# wahmodgnd.net
KiCad netlist of a schematic drawn in EAGLE
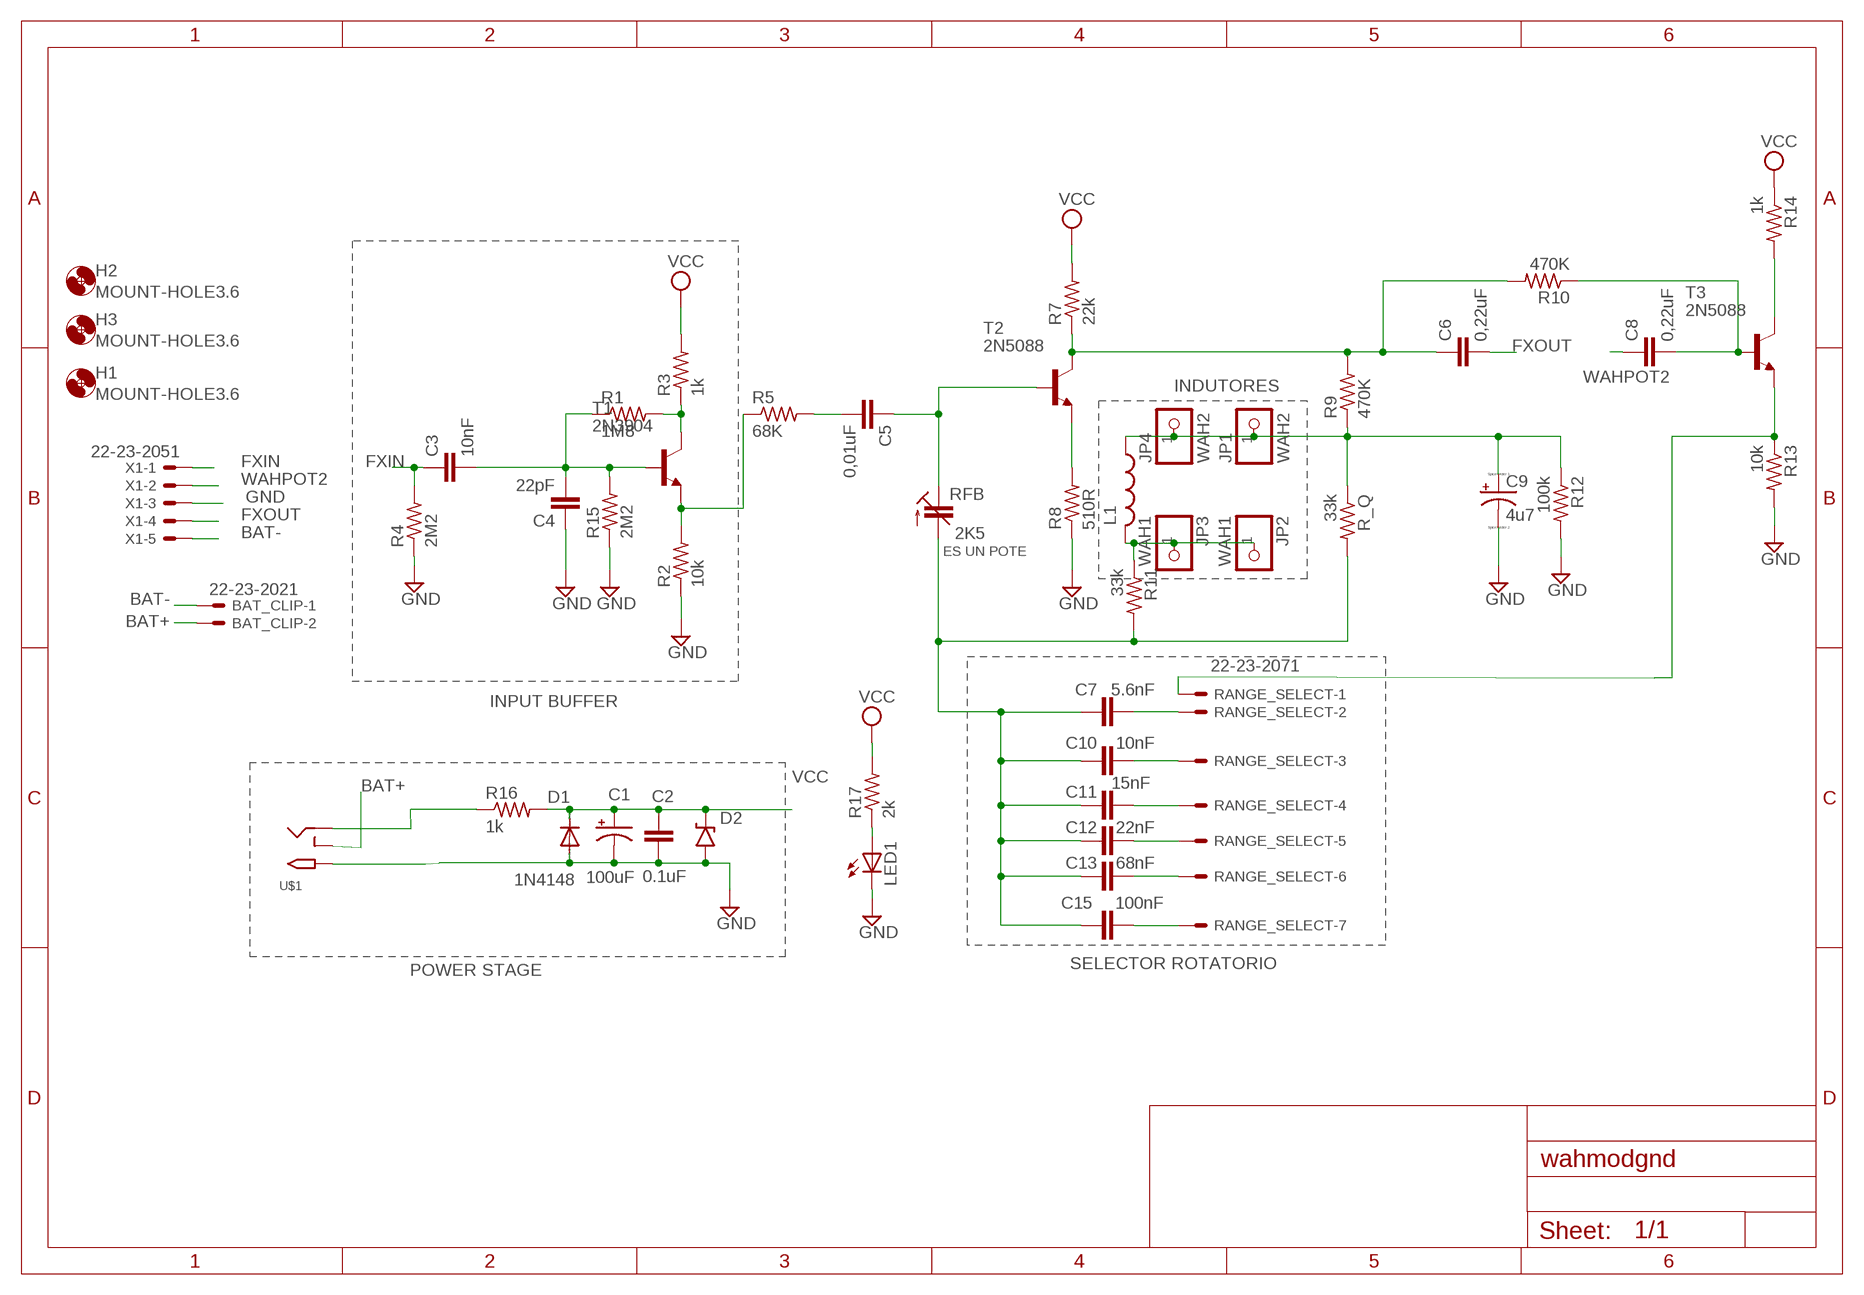
[diagram p0: schematic, sheet 1]

(export (version "E")
  (design (tool "Eeschema 10.0.6"))
  (components
    (comp (ref "BAT_CLIP")
      (value "22-23-2021")
      (footprint "eagle-import:22-23-2021")
      (fields (field (name "MF") "MOLEX"))
      (libsource (lib "eagle-import") (part "22-23-2021"))
    )
    (comp (ref "C1")
      (value "100uF")
      (footprint "eagle-import:E2,5-5")
      (libsource (lib "eagle-import") (part "CPOL-USE2.5-5"))
    )
    (comp (ref "C2")
      (value "0.1uF")
      (footprint "eagle-import:C025-025X050")
      (libsource (lib "eagle-import") (part "C-EU025-025X050"))
    )
    (comp (ref "C3")
      (value "10nF")
      (footprint "eagle-import:C050-025X075")
      (libsource (lib "eagle-import") (part "resistor_C-EU050-025X075"))
    )
    (comp (ref "C4")
      (value "22pF")
      (footprint "eagle-import:C050-025X075")
      (libsource (lib "eagle-import") (part "resistor_C-EU050-025X075"))
    )
    (comp (ref "C5")
      (value "0,01uF")
      (footprint "eagle-import:C050-035X075")
      (libsource (lib "eagle-import") (part "resistor_C-EU050-035X075"))
    )
    (comp (ref "C6")
      (value "0,22uF")
      (footprint "eagle-import:C050-035X075")
      (libsource (lib "eagle-import") (part "resistor_C-EU050-035X075"))
    )
    (comp (ref "C7")
      (value "5.6nF")
      (footprint "eagle-import:C050-030X075")
      (libsource (lib "eagle-import") (part "resistor_C-EU050-030X075"))
    )
    (comp (ref "C8")
      (value "0,22uF")
      (footprint "eagle-import:C050-035X075")
      (libsource (lib "eagle-import") (part "resistor_C-EU050-035X075"))
    )
    (comp (ref "C9")
      (value "4u7")
      (footprint "eagle-import:E2,5-6")
      (libsource (lib "eagle-import") (part "resistor_CPOL-USE2.5-6"))
    )
    (comp (ref "C10")
      (value "10nF")
      (footprint "eagle-import:C050-030X075")
      (libsource (lib "eagle-import") (part "resistor_C-EU050-030X075"))
    )
    (comp (ref "C11")
      (value "15nF")
      (footprint "eagle-import:C050-030X075")
      (libsource (lib "eagle-import") (part "resistor_C-EU050-030X075"))
    )
    (comp (ref "C12")
      (value "22nF")
      (footprint "eagle-import:C050-030X075")
      (libsource (lib "eagle-import") (part "resistor_C-EU050-030X075"))
    )
    (comp (ref "C13")
      (value "68nF")
      (footprint "eagle-import:C050-030X075")
      (libsource (lib "eagle-import") (part "resistor_C-EU050-030X075"))
    )
    (comp (ref "C15")
      (value "100nF")
      (footprint "eagle-import:C050-030X075")
      (libsource (lib "eagle-import") (part "resistor_C-EU050-030X075"))
    )
    (comp (ref "D1")
      (value "1N4148")
      (footprint "eagle-import:DO35-7")
      (libsource (lib "eagle-import") (part "1N4148DO35-7"))
    )
    (comp (ref "D2")
      (value "1N9ZENER")
      (footprint "eagle-import:DO35-3")
      (libsource (lib "eagle-import") (part "1N9ZENER"))
    )
    (comp (ref "H1")
      (value "MOUNT-HOLE3.6")
      (footprint "eagle-import:3,6")
      (libsource (lib "eagle-import") (part "MOUNT-HOLE3.6"))
    )
    (comp (ref "H2")
      (value "MOUNT-HOLE3.6")
      (footprint "eagle-import:3,6")
      (libsource (lib "eagle-import") (part "MOUNT-HOLE3.6"))
    )
    (comp (ref "H3")
      (value "MOUNT-HOLE3.6")
      (footprint "eagle-import:3,6")
      (libsource (lib "eagle-import") (part "MOUNT-HOLE3.6"))
    )
    (comp (ref "JP1")
      (value "WAH2")
      (footprint "eagle-import:1X01")
      (libsource (lib "eagle-import") (part "PINHD-1X1"))
    )
    (comp (ref "JP2")
      (value "WAH1")
      (footprint "eagle-import:1X01")
      (libsource (lib "eagle-import") (part "PINHD-1X1"))
    )
    (comp (ref "JP3")
      (value "WAH1")
      (footprint "eagle-import:1X01")
      (libsource (lib "eagle-import") (part "PINHD-1X1"))
    )
    (comp (ref "JP4")
      (value "WAH2")
      (footprint "eagle-import:1X01")
      (libsource (lib "eagle-import") (part "PINHD-1X1"))
    )
    (comp (ref "L1")
      (value "WAH")
      (footprint "eagle-import:WAH")
      (libsource (lib "eagle-import") (part "WAH"))
    )
    (comp (ref "LED1")
      (value "TLLY4400")
      (footprint "eagle-import:LED3MM")
      (fields (field (name "MF") "VISHAY SEMICONDUCTOR"))
      (libsource (lib "eagle-import") (part "TLLY4400"))
    )
    (comp (ref "R1")
      (value "1M8")
      (footprint "eagle-import:0204_7")
      (libsource (lib "eagle-import") (part "R-US_0204/7"))
    )
    (comp (ref "R2")
      (value "10k")
      (footprint "eagle-import:0204_7")
      (libsource (lib "eagle-import") (part "R-US_0204/7"))
    )
    (comp (ref "R3")
      (value "1k")
      (footprint "eagle-import:0204_7")
      (libsource (lib "eagle-import") (part "R-US_0204/7"))
    )
    (comp (ref "R4")
      (value "2M2")
      (footprint "eagle-import:0204_7")
      (libsource (lib "eagle-import") (part "R-US_0204/7"))
    )
    (comp (ref "R5")
      (value "68K")
      (footprint "eagle-import:0204_7")
      (libsource (lib "eagle-import") (part "R-US_0204/7"))
    )
    (comp (ref "R7")
      (value "22k")
      (footprint "eagle-import:0204_7")
      (libsource (lib "eagle-import") (part "R-US_0204/7"))
    )
    (comp (ref "R8")
      (value "510R")
      (footprint "eagle-import:0204_7")
      (libsource (lib "eagle-import") (part "R-US_0204/7"))
    )
    (comp (ref "R9")
      (value "470K")
      (footprint "eagle-import:0204_7")
      (libsource (lib "eagle-import") (part "R-US_0204/7"))
    )
    (comp (ref "R10")
      (value "470K")
      (footprint "eagle-import:0204_7")
      (libsource (lib "eagle-import") (part "R-US_0204/7"))
    )
    (comp (ref "R11")
      (value "33k")
      (footprint "eagle-import:0204_7")
      (libsource (lib "eagle-import") (part "R-US_0204/7"))
    )
    (comp (ref "R12")
      (value "100k")
      (footprint "eagle-import:0204_7")
      (libsource (lib "eagle-import") (part "R-US_0204/7"))
    )
    (comp (ref "R13")
      (value "10k")
      (footprint "eagle-import:0204_7")
      (libsource (lib "eagle-import") (part "R-US_0204/7"))
    )
    (comp (ref "R14")
      (value "1k")
      (footprint "eagle-import:0204_7")
      (libsource (lib "eagle-import") (part "R-US_0204/7"))
    )
    (comp (ref "R15")
      (value "2M2")
      (footprint "eagle-import:0204_7")
      (libsource (lib "eagle-import") (part "R-US_0204/7"))
    )
    (comp (ref "R16")
      (value "1k")
      (footprint "eagle-import:0204_7")
      (libsource (lib "eagle-import") (part "R-US_0204/7"))
    )
    (comp (ref "R17")
      (value "2k")
      (footprint "eagle-import:0204_7")
      (libsource (lib "eagle-import") (part "R-US_0204/7"))
    )
    (comp (ref "RANGE_SELECT")
      (value "22-23-2071")
      (footprint "eagle-import:22-23-2071")
      (fields (field (name "MF") "MOLEX"))
      (libsource (lib "eagle-import") (part "22-23-2071"))
    )
    (comp (ref "RFB")
      (value "2K5")
      (footprint "eagle-import:CTRIM808-BC7.5")
      (libsource (lib "eagle-import") (part "C-TRIMM808-7.5"))
    )
    (comp (ref "R_Q")
      (value "33k")
      (footprint "eagle-import:0204_7")
      (libsource (lib "eagle-import") (part "R-US_0204/7"))
    )
    (comp (ref "T1")
      (value "2N3904")
      (footprint "eagle-import:TO92")
      (libsource (lib "eagle-import") (part "2N3904"))
    )
    (comp (ref "T2")
      (value "2N5088")
      (footprint "eagle-import:TO92")
      (libsource (lib "eagle-import") (part "2N5088"))
    )
    (comp (ref "T3")
      (value "2N5088")
      (footprint "eagle-import:TO92")
      (libsource (lib "eagle-import") (part "2N5088"))
    )
    (comp (ref "U$1")
      (value "2.1MMJACKTHM")
      (footprint "eagle-import:PJ-102A")
      (libsource (lib "eagle-import") (part "2.1MMJACKTHM"))
    )
    (comp (ref "X1")
      (value "22-23-2051")
      (footprint "eagle-import:22-23-2051")
      (fields (field (name "MF") "MOLEX"))
      (libsource (lib "eagle-import") (part "22-23-2051"))
    )
  )
  (nets
    (net (code "1") (name "/BAT+") (class "Default")
      (node (ref "BAT_CLIP") (pin "2") (pinfunction "S_2") (pintype "passive"))
      (node (ref "U$1") (pin "RING_SW") (pinfunction "RING_SW_RING_SW") (pintype "bidirectional"))
    )
    (net (code "2") (name "/BAT-") (class "Default")
      (node (ref "BAT_CLIP") (pin "1") (pinfunction "S_1") (pintype "passive"))
      (node (ref "X1") (pin "5") (pinfunction "S_5") (pintype "passive"))
    )
    (net (code "3") (name "/FXIN") (class "Default")
      (node (ref "C3") (pin "1") (pinfunction "1_1") (pintype "passive"))
      (node (ref "R4") (pin "2") (pinfunction "2_2") (pintype "passive"))
      (node (ref "X1") (pin "1") (pinfunction "S_1") (pintype "passive"))
    )
    (net (code "4") (name "/FXOUT") (class "Default")
      (node (ref "C6") (pin "2") (pinfunction "2_2") (pintype "passive"))
      (node (ref "X1") (pin "4") (pinfunction "S_4") (pintype "passive"))
    )
    (net (code "5") (name "/WAHPOT2") (class "Default")
      (node (ref "C8") (pin "1") (pinfunction "1_1") (pintype "passive"))
      (node (ref "X1") (pin "2") (pinfunction "S_2") (pintype "passive"))
    )
    (net (code "6") (name "GND") (class "Default")
      (node (ref "C1") (pin "-") (pinfunction "-_-") (pintype "passive"))
      (node (ref "C2") (pin "2") (pinfunction "2_2") (pintype "passive"))
      (node (ref "C4") (pin "1") (pinfunction "1_1") (pintype "passive"))
      (node (ref "C9") (pin "-") (pinfunction "-_-") (pintype "passive"))
      (node (ref "D1") (pin "A") (pinfunction "A_A") (pintype "passive"))
      (node (ref "D2") (pin "A") (pinfunction "A_A") (pintype "passive"))
      (node (ref "LED1") (pin "K") (pinfunction "C_K") (pintype "passive"))
      (node (ref "R12") (pin "2") (pinfunction "2_2") (pintype "passive"))
      (node (ref "R13") (pin "2") (pinfunction "2_2") (pintype "passive"))
      (node (ref "R15") (pin "1") (pinfunction "1_1") (pintype "passive"))
      (node (ref "R2") (pin "1") (pinfunction "1_1") (pintype "passive"))
      (node (ref "R4") (pin "1") (pinfunction "1_1") (pintype "passive"))
      (node (ref "R8") (pin "1") (pinfunction "1_1") (pintype "passive"))
      (node (ref "U$1") (pin "TIP") (pinfunction "TIP_TIP") (pintype "bidirectional"))
      (node (ref "X1") (pin "3") (pinfunction "S_3") (pintype "passive"))
    )
    (net (code "7") (name "Net-(C5-Pad2)") (class "Default")
      (node (ref "C5") (pin "2") (pinfunction "2_2") (pintype "passive"))
      (node (ref "R5") (pin "2") (pinfunction "2_2") (pintype "passive"))
    )
    (net (code "8") (name "Net-(C9-Pad+)") (class "Default")
      (node (ref "C9") (pin "+") (pinfunction "+_+") (pintype "passive"))
      (node (ref "JP1") (pin "1") (pinfunction "1_1") (pintype "passive"))
      (node (ref "JP4") (pin "1") (pinfunction "1_1") (pintype "passive"))
      (node (ref "L1") (pin "1") (pinfunction "1_1") (pintype "passive"))
      (node (ref "R12") (pin "1") (pinfunction "1_1") (pintype "passive"))
      (node (ref "R9") (pin "1") (pinfunction "1_1") (pintype "passive"))
      (node (ref "R_Q") (pin "1") (pinfunction "1_1") (pintype "passive"))
    )
    (net (code "9") (name "Net-(JP2-Pad1)") (class "Default")
      (node (ref "JP2") (pin "1") (pinfunction "1_1") (pintype "passive"))
      (node (ref "JP3") (pin "1") (pinfunction "1_1") (pintype "passive"))
      (node (ref "L1") (pin "2") (pinfunction "2_2") (pintype "passive"))
      (node (ref "R11") (pin "1") (pinfunction "1_1") (pintype "passive"))
    )
    (net (code "10") (name "Net-(LED1-PadA)") (class "Default")
      (node (ref "LED1") (pin "A") (pinfunction "A_A") (pintype "passive"))
      (node (ref "R17") (pin "1") (pinfunction "1_1") (pintype "passive"))
    )
    (net (code "11") (name "Net-(R16-Pad1)") (class "Default")
      (node (ref "R16") (pin "1") (pinfunction "1_1") (pintype "passive"))
      (node (ref "U$1") (pin "RING") (pinfunction "RING_RING") (pintype "bidirectional"))
    )
    (net (code "12") (name "Net-(RANGE_SELECTA-S)") (class "Default")
      (node (ref "R13") (pin "1") (pinfunction "1_1") (pintype "passive"))
      (node (ref "RANGE_SELECT") (pin "1") (pinfunction "S_1") (pintype "passive"))
      (node (ref "T3") (pin "3") (pinfunction "E_3") (pintype "passive"))
    )
    (net (code "13") (name "Net-(RANGE_SELECTB-S)") (class "Default")
      (node (ref "C7") (pin "2") (pinfunction "2_2") (pintype "passive"))
      (node (ref "RANGE_SELECT") (pin "2") (pinfunction "S_2") (pintype "passive"))
    )
    (net (code "14") (name "Net-(RANGE_SELECTC-S)") (class "Default")
      (node (ref "C10") (pin "2") (pinfunction "2_2") (pintype "passive"))
      (node (ref "RANGE_SELECT") (pin "3") (pinfunction "S_3") (pintype "passive"))
    )
    (net (code "15") (name "Net-(RANGE_SELECTD-S)") (class "Default")
      (node (ref "C11") (pin "2") (pinfunction "2_2") (pintype "passive"))
      (node (ref "RANGE_SELECT") (pin "4") (pinfunction "S_4") (pintype "passive"))
    )
    (net (code "16") (name "Net-(RANGE_SELECTE-S)") (class "Default")
      (node (ref "C12") (pin "2") (pinfunction "2_2") (pintype "passive"))
      (node (ref "RANGE_SELECT") (pin "5") (pinfunction "S_5") (pintype "passive"))
    )
    (net (code "17") (name "Net-(RANGE_SELECTF-S)") (class "Default")
      (node (ref "C13") (pin "2") (pinfunction "2_2") (pintype "passive"))
      (node (ref "RANGE_SELECT") (pin "6") (pinfunction "S_6") (pintype "passive"))
    )
    (net (code "18") (name "Net-(RANGE_SELECTG-S)") (class "Default")
      (node (ref "C15") (pin "2") (pinfunction "2_2") (pintype "passive"))
      (node (ref "RANGE_SELECT") (pin "7") (pinfunction "S_7") (pintype "passive"))
    )
    (net (code "19") (name "Net-(RFB-A)") (class "Default")
      (node (ref "C10") (pin "1") (pinfunction "1_1") (pintype "passive"))
      (node (ref "C11") (pin "1") (pinfunction "1_1") (pintype "passive"))
      (node (ref "C12") (pin "1") (pinfunction "1_1") (pintype "passive"))
      (node (ref "C13") (pin "1") (pinfunction "1_1") (pintype "passive"))
      (node (ref "C15") (pin "1") (pinfunction "1_1") (pintype "passive"))
      (node (ref "C7") (pin "1") (pinfunction "1_1") (pintype "passive"))
      (node (ref "R11") (pin "2") (pinfunction "2_2") (pintype "passive"))
      (node (ref "RFB") (pin "2") (pinfunction "A_2") (pintype "passive"))
      (node (ref "R_Q") (pin "2") (pinfunction "2_2") (pintype "passive"))
    )
    (net (code "20") (name "Net-(RFB-E)") (class "Default")
      (node (ref "C5") (pin "1") (pinfunction "1_1") (pintype "passive"))
      (node (ref "RFB") (pin "1") (pinfunction "E_1") (pintype "passive"))
      (node (ref "T2") (pin "2") (pinfunction "B_2") (pintype "passive"))
    )
    (net (code "21") (name "Net-(T1-B)") (class "Default")
      (node (ref "C3") (pin "2") (pinfunction "2_2") (pintype "passive"))
      (node (ref "C4") (pin "2") (pinfunction "2_2") (pintype "passive"))
      (node (ref "R1") (pin "1") (pinfunction "1_1") (pintype "passive"))
      (node (ref "R15") (pin "2") (pinfunction "2_2") (pintype "passive"))
      (node (ref "T1") (pin "2") (pinfunction "B_2") (pintype "passive"))
    )
    (net (code "22") (name "Net-(T1-C)") (class "Default")
      (node (ref "R1") (pin "2") (pinfunction "2_2") (pintype "passive"))
      (node (ref "R3") (pin "1") (pinfunction "1_1") (pintype "passive"))
      (node (ref "T1") (pin "1") (pinfunction "C_1") (pintype "passive"))
    )
    (net (code "23") (name "Net-(T1-E)") (class "Default")
      (node (ref "R2") (pin "2") (pinfunction "2_2") (pintype "passive"))
      (node (ref "R5") (pin "1") (pinfunction "1_1") (pintype "passive"))
      (node (ref "T1") (pin "3") (pinfunction "E_3") (pintype "passive"))
    )
    (net (code "24") (name "Net-(T2-C)") (class "Default")
      (node (ref "C6") (pin "1") (pinfunction "1_1") (pintype "passive"))
      (node (ref "R10") (pin "2") (pinfunction "2_2") (pintype "passive"))
      (node (ref "R7") (pin "1") (pinfunction "1_1") (pintype "passive"))
      (node (ref "R9") (pin "2") (pinfunction "2_2") (pintype "passive"))
      (node (ref "T2") (pin "1") (pinfunction "C_1") (pintype "passive"))
    )
    (net (code "25") (name "Net-(T2-E)") (class "Default")
      (node (ref "R8") (pin "2") (pinfunction "2_2") (pintype "passive"))
      (node (ref "T2") (pin "3") (pinfunction "E_3") (pintype "passive"))
    )
    (net (code "26") (name "Net-(T3-B)") (class "Default")
      (node (ref "C8") (pin "2") (pinfunction "2_2") (pintype "passive"))
      (node (ref "R10") (pin "1") (pinfunction "1_1") (pintype "passive"))
      (node (ref "T3") (pin "2") (pinfunction "B_2") (pintype "passive"))
    )
    (net (code "27") (name "Net-(T3-C)") (class "Default")
      (node (ref "R14") (pin "2") (pinfunction "2_2") (pintype "passive"))
      (node (ref "T3") (pin "1") (pinfunction "C_1") (pintype "passive"))
    )
    (net (code "28") (name "VCC") (class "Default")
      (node (ref "C1") (pin "+") (pinfunction "+_+") (pintype "passive"))
      (node (ref "C2") (pin "1") (pinfunction "1_1") (pintype "passive"))
      (node (ref "D1") (pin "C") (pinfunction "C_C") (pintype "passive"))
      (node (ref "D2") (pin "C") (pinfunction "C_C") (pintype "passive"))
      (node (ref "R14") (pin "1") (pinfunction "1_1") (pintype "passive"))
      (node (ref "R16") (pin "2") (pinfunction "2_2") (pintype "passive"))
      (node (ref "R17") (pin "2") (pinfunction "2_2") (pintype "passive"))
      (node (ref "R3") (pin "2") (pinfunction "2_2") (pintype "passive"))
      (node (ref "R7") (pin "2") (pinfunction "2_2") (pintype "passive"))
    )
  )
)
